# LPEDT_revA1_bikeit_MCU_POWER.net
KiCad netlist of a schematic drawn in Altium Designer
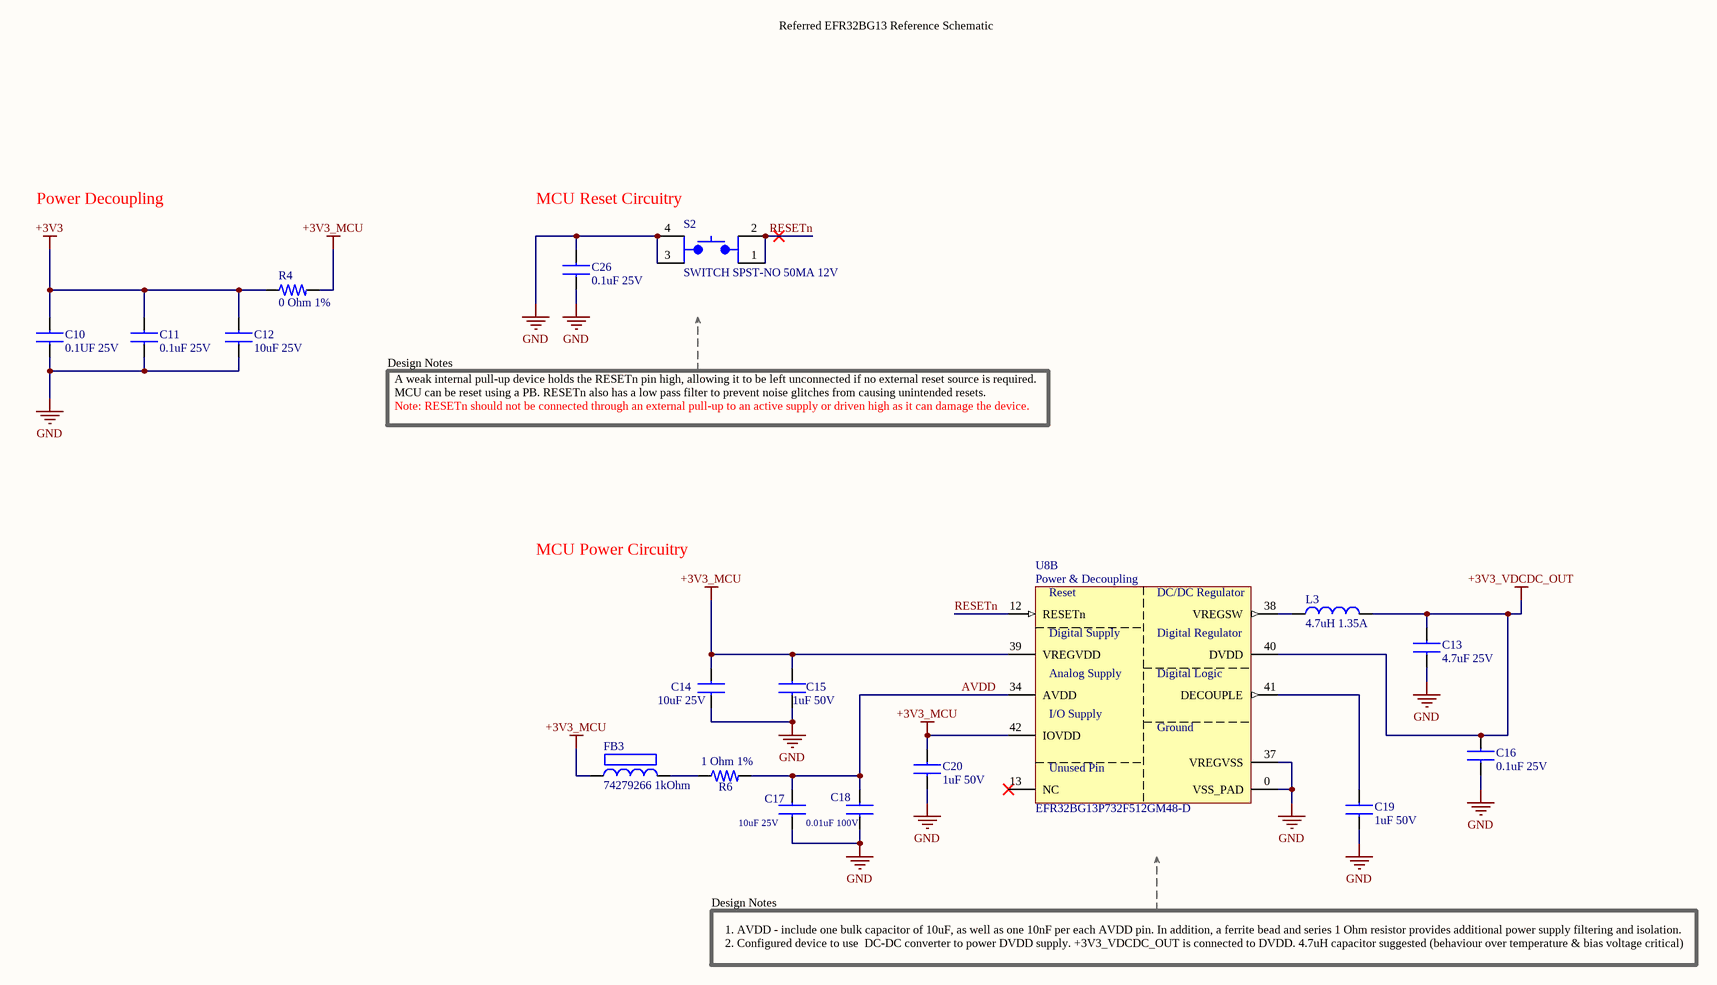
[diagram p0: LPEDT_revA1_bikeit_MCU_POWER.SchDoc]

(export (version "E")
  (design (tool "Eeschema 10.0.6"))
  (components
    (comp (ref "C10")
      (value "0.1UF 25V")
      (footprint "CAP_0603_1.60mm*0.80mm")
      (description "CAP CER 0.1UF 25V X7R 0603")
      (fields
        (field (name "MANUFACTURER") "Murata")
        (field (name "MANUFACTURER PART NUMBER") "GCJ188R71E104KA12D")
      )
      (libsource (lib "LPEDT_revA1_bikeit_IL") (part "GCJ188R71E104KA12D"))
    )
    (comp (ref "C11")
      (value "0.1uF 25V")
      (footprint "CAP_0603_1.60mm*0.80mm")
      (description "CAP CER 0.1UF 25V X7R 0603")
      (fields
        (field (name "MANUFACTURER") "Murata")
        (field (name "MANUFACTURER PART NUMBER") "GCJ188R71E104KA12D")
      )
      (libsource (lib "LPEDT_revA1_bikeit_IL") (part "GCJ188R71E104KA12D"))
    )
    (comp (ref "C12")
      (value "10uF 25V")
      (footprint "CAP_0805_2MM")
      (description "CAP CER 10UF 25V X5R 0805")
      (fields
        (field (name "MANUFACTURER") "Murata")
        (field (name "MANUFACTURER PART NUMBER") "GRM21BR61E106KA73K")
      )
      (libsource (lib "LPEDT_revA1_bikeit_IL") (part "GRM21BR61E106KA73K"))
    )
    (comp (ref "C13")
      (value "4.7uF 25V")
      (footprint "CAP_0603_1.60mm*0.80mm")
      (description "Cap Ceramic 0603 4.7 uF 25 V ±10 % Tolerance X5R SMT Multilayer Ceramic Capacitor")
      (fields
        (field (name "MANUFACTURER") "Murata")
        (field (name "MANUFACTURER PART NUMBER") "GRM188R61E475KE11D")
      )
      (libsource (lib "LPEDT_revA1_bikeit_IL") (part "GRM188R61E475KE11D"))
    )
    (comp (ref "C14")
      (value "10uF 25V")
      (footprint "CAP_0805_2MM")
      (description "CAP CER 10UF 25V X5R 0805")
      (fields
        (field (name "MANUFACTURER") "Murata")
        (field (name "MANUFACTURER PART NUMBER") "GRM21BR61E106KA73K")
      )
      (libsource (lib "LPEDT_revA1_bikeit_IL") (part "GRM21BR61E106KA73K"))
    )
    (comp (ref "C15")
      (value "1uF 50V")
      (footprint "CAP_0603_1.60mm*0.80mm")
      (description "CAP, MLCC, AEC-Q200, X5R, 1uF, 50V, 0603")
      (fields
        (field (name "MANUFACTURER") "Murata")
        (field (name "MANUFACTURER PART NUMBER") "GRT188R61H105KE13D")
      )
      (libsource (lib "LPEDT_revA1_bikeit_IL") (part "GRT188R61H105KE13D"))
    )
    (comp (ref "C16")
      (value "0.1uF 25V")
      (footprint "CAP_0603_1.60mm*0.80mm")
      (description "CAP CER 0.1UF 25V X7R 0603")
      (fields
        (field (name "MANUFACTURER") "Murata")
        (field (name "MANUFACTURER PART NUMBER") "GCJ188R71E104KA12D")
      )
      (libsource (lib "LPEDT_revA1_bikeit_IL") (part "GCJ188R71E104KA12D"))
    )
    (comp (ref "C17")
      (value "10uF 25V")
      (footprint "CAP_0805_2MM")
      (description "CAP CER 10UF 25V X5R 0805")
      (fields
        (field (name "MANUFACTURER") "Murata")
        (field (name "MANUFACTURER PART NUMBER") "GRM21BR61E106KA73K")
      )
      (libsource (lib "LPEDT_revA1_bikeit_IL") (part "GRM21BR61E106KA73K"))
    )
    (comp (ref "C18")
      (value "0.01uF 100V")
      (footprint "CAP_0603_1.60mm*0.80mm")
      (description "Multilayer Ceramic Capacitor, AEC-Q200 GCM Series, 0.01 F, 10%, X7R, 100 V RoHS Compliant: Yes")
      (fields
        (field (name "MANUFACTURER") "Murata")
        (field (name "MANUFACTURER PART NUMBER") "GCM188R72A103KA37D")
      )
      (libsource (lib "LPEDT_revA1_bikeit_IL") (part "GCM188R72A103KA37D"))
    )
    (comp (ref "C19")
      (value "1uF 50V")
      (footprint "CAP_0603_1.60mm*0.80mm")
      (description "CAP, MLCC, AEC-Q200, X5R, 1uF, 50V, 0603")
      (fields
        (field (name "MANUFACTURER") "Murata")
        (field (name "MANUFACTURER PART NUMBER") "GRT188R61H105KE13D")
      )
      (libsource (lib "LPEDT_revA1_bikeit_IL") (part "GRT188R61H105KE13D"))
    )
    (comp (ref "C20")
      (value "1uF 50V")
      (footprint "CAP_0603_1.60mm*0.80mm")
      (description "CAP, MLCC, AEC-Q200, X5R, 1uF, 50V, 0603")
      (fields
        (field (name "MANUFACTURER") "Murata")
        (field (name "MANUFACTURER PART NUMBER") "GRT188R61H105KE13D")
      )
      (libsource (lib "LPEDT_revA1_bikeit_IL") (part "GRT188R61H105KE13D"))
    )
    (comp (ref "C26")
      (value "0.1uF 25V")
      (footprint "CAP_0603_1.60mm*0.80mm")
      (description "CAP CER 0.1UF 25V X7R 0603")
      (fields
        (field (name "MANUFACTURER") "Murata")
        (field (name "MANUFACTURER PART NUMBER") "GCJ188R71E104KA12D")
      )
      (libsource (lib "LPEDT_revA1_bikeit_IL") (part "GCJ188R71E104KA12D"))
    )
    (comp (ref "FB3")
      (value "74279266 1kOhm")
      (footprint "FB_0603_1.60mm*0.80mm")
      (description "Ferrite Bead, 0603 [1608 Metric], 1 kohm, 200 mA, WE-CBF Series, 0.6 ohm, ± 25%")
      (fields
        (field (name "MANUFACTURER") "Wurth Electronics")
        (field (name "MANUFACTURER PART NUMBER") "74279266")
      )
      (libsource (lib "LPEDT_revA1_bikeit_IL") (part "74279266"))
    )
    (comp (ref "L3")
      (value "4.7uH 1.35A")
      (description "Fixed Inductors WE-TPC 2828 4.7uH 1.35A .1Ohm")
      (fields
        (field (name "MANUFACTURER") "Wurth Electronics")
        (field (name "MANUFACTURER PART NUMBER") "744025004")
      )
      (libsource (lib "LPEDT_revA1_bikeit_IL") (part "744025004"))
    )
    (comp (ref "R4")
      (value "0 Ohm 1%")
      (footprint "RESC1005X04N")
      (description "RES 0 OHM JUMPER 1/16W 0402")
      (fields
        (field (name "MANUFACTURER") "Stackpole Electronics")
        (field (name "MANUFACTURER PART NUMBER") "RMCF0402ZT0R00")
      )
      (libsource (lib "LPEDT_revA1_bikeit_IL") (part "RMCF0402ZT0R00"))
    )
    (comp (ref "R6")
      (value "1 Ohm 1%")
      (footprint "RES_0603_1608X06")
      (description "RES SMD 1 OHM 1% 1/10W 0603")
      (fields
        (field (name "MANUFACTURER") "Panasonic")
        (field (name "MANUFACTURER PART NUMBER") "ERJ-3RQF1R0V")
      )
      (libsource (lib "LPEDT_revA1_bikeit_IL") (part "ERJ-3RQF1R0V"))
    )
    (comp (ref "S2")
      (value "SWITCH SPST-NO 50MA 12V")
      (footprint "SW_TL3305AF260QG")
      (description "SWITCH TACTILE SPST-NO 50MA 12V")
      (fields
        (field (name "MANUFACTURER") "E-Switch")
        (field (name "MANUFACTURER PART NUMBER") "TL3305AF260QG")
      )
      (libsource (lib "LPEDT_revA1_bikeit_IL") (part "TL3305AF260QG"))
    )
    (comp (ref "U8")
      (value "EFR32BG13P732F512GM48-D")
      (footprint "QFN50P700X700X90_HS-49N")
      (description "BLUE GECKO QFN48 2.4 GHZ 512KB 6")
      (fields (field (name "MANUFACTURER") "Silicon Labs"))
      (libsource (lib "LPEDT_revA1_bikeit") (part "EFR32BG13P732F512GM48-D"))
    )
  )
  (nets
    (net (code "1") (name "+3V3") (class "Default")
      (node (ref "C10") (pin "1") (pinfunction "1_1") (pintype "passive"))
      (node (ref "C11") (pin "1") (pinfunction "1_1") (pintype "passive"))
      (node (ref "C12") (pin "1") (pinfunction "1_1") (pintype "passive"))
      (node (ref "R4") (pin "1") (pinfunction "1_1") (pintype "passive"))
    )
    (net (code "2") (name "+3V3_MCU") (class "Default")
      (node (ref "C14") (pin "1") (pinfunction "1_1") (pintype "passive"))
      (node (ref "C15") (pin "1") (pinfunction "1_1") (pintype "passive"))
      (node (ref "C20") (pin "1") (pinfunction "1_1") (pintype "passive"))
      (node (ref "FB3") (pin "1") (pinfunction "1_1") (pintype "passive"))
      (node (ref "R4") (pin "2") (pinfunction "2_2") (pintype "passive"))
      (node (ref "U8") (pin "39") (pinfunction "VREGVDD_39") (pintype "power_in"))
      (node (ref "U8") (pin "42") (pinfunction "IOVDD_42") (pintype "power_in"))
    )
    (net (code "3") (name "+3V3_VDCDC_OUT") (class "Default")
      (node (ref "C13") (pin "1") (pinfunction "1_1") (pintype "passive"))
      (node (ref "C16") (pin "1") (pinfunction "1_1") (pintype "passive"))
      (node (ref "L3") (pin "2") (pinfunction "2_2") (pintype "passive"))
      (node (ref "U8") (pin "40") (pinfunction "DVDD_40") (pintype "power_in"))
    )
    (net (code "4") (name "/AVDD") (class "Default")
      (node (ref "C17") (pin "1") (pinfunction "1_1") (pintype "passive"))
      (node (ref "C18") (pin "1") (pinfunction "1_1") (pintype "passive"))
      (node (ref "R6") (pin "2") (pinfunction "2_2") (pintype "passive"))
      (node (ref "U8") (pin "34") (pinfunction "AVDD_34") (pintype "power_in"))
    )
    (net (code "5") (name "/RESETn") (class "Default")
      (node (ref "S2") (pin "1") (pinfunction "1_1") (pintype "passive"))
      (node (ref "S2") (pin "2") (pinfunction "2_2") (pintype "passive"))
      (node (ref "U8") (pin "12") (pinfunction "RESETn_12") (pintype "input"))
    )
    (net (code "6") (name "GND") (class "Default")
      (node (ref "C10") (pin "2") (pinfunction "2_2") (pintype "passive"))
      (node (ref "C11") (pin "2") (pinfunction "2_2") (pintype "passive"))
      (node (ref "C12") (pin "2") (pinfunction "2_2") (pintype "passive"))
      (node (ref "C13") (pin "2") (pinfunction "2_2") (pintype "passive"))
      (node (ref "C14") (pin "2") (pinfunction "2_2") (pintype "passive"))
      (node (ref "C15") (pin "2") (pinfunction "2_2") (pintype "passive"))
      (node (ref "C16") (pin "2") (pinfunction "2_2") (pintype "passive"))
      (node (ref "C17") (pin "2") (pinfunction "2_2") (pintype "passive"))
      (node (ref "C18") (pin "2") (pinfunction "2_2") (pintype "passive"))
      (node (ref "C19") (pin "2") (pinfunction "2_2") (pintype "passive"))
      (node (ref "C20") (pin "2") (pinfunction "2_2") (pintype "passive"))
      (node (ref "C26") (pin "1") (pinfunction "1_1") (pintype "passive"))
      (node (ref "C26") (pin "2") (pinfunction "2_2") (pintype "passive"))
      (node (ref "S2") (pin "3") (pinfunction "3_3") (pintype "passive"))
      (node (ref "S2") (pin "4") (pinfunction "4_4") (pintype "passive"))
      (node (ref "U8") (pin "0") (pinfunction "VSS_PAD_0") (pintype "passive"))
      (node (ref "U8") (pin "37") (pinfunction "VREGVSS_37") (pintype "passive"))
    )
    (net (code "7") (name "Net-(FB3-Pad2)") (class "Default")
      (node (ref "FB3") (pin "2") (pinfunction "2_2") (pintype "passive"))
      (node (ref "R6") (pin "1") (pinfunction "1_1") (pintype "passive"))
    )
    (net (code "8") (name "Net-(U8B-DECOUPLE)") (class "Default")
      (node (ref "C19") (pin "1") (pinfunction "1_1") (pintype "passive"))
      (node (ref "U8") (pin "41") (pinfunction "DECOUPLE_41") (pintype "output"))
    )
    (net (code "9") (name "Net-(U8B-VREGSW)") (class "Default")
      (node (ref "L3") (pin "1") (pinfunction "1_1") (pintype "passive"))
      (node (ref "U8") (pin "38") (pinfunction "VREGSW_38") (pintype "output"))
    )
    (net (code "10") (name "unconnected-(U8B-NC-Pad13)") (class "Default")
      (node (ref "U8") (pin "13") (pinfunction "NC_13") (pintype "passive+no_connect"))
    )
  )
)
